# NPaddle.net
KiCad netlist of a schematic drawn in EAGLE
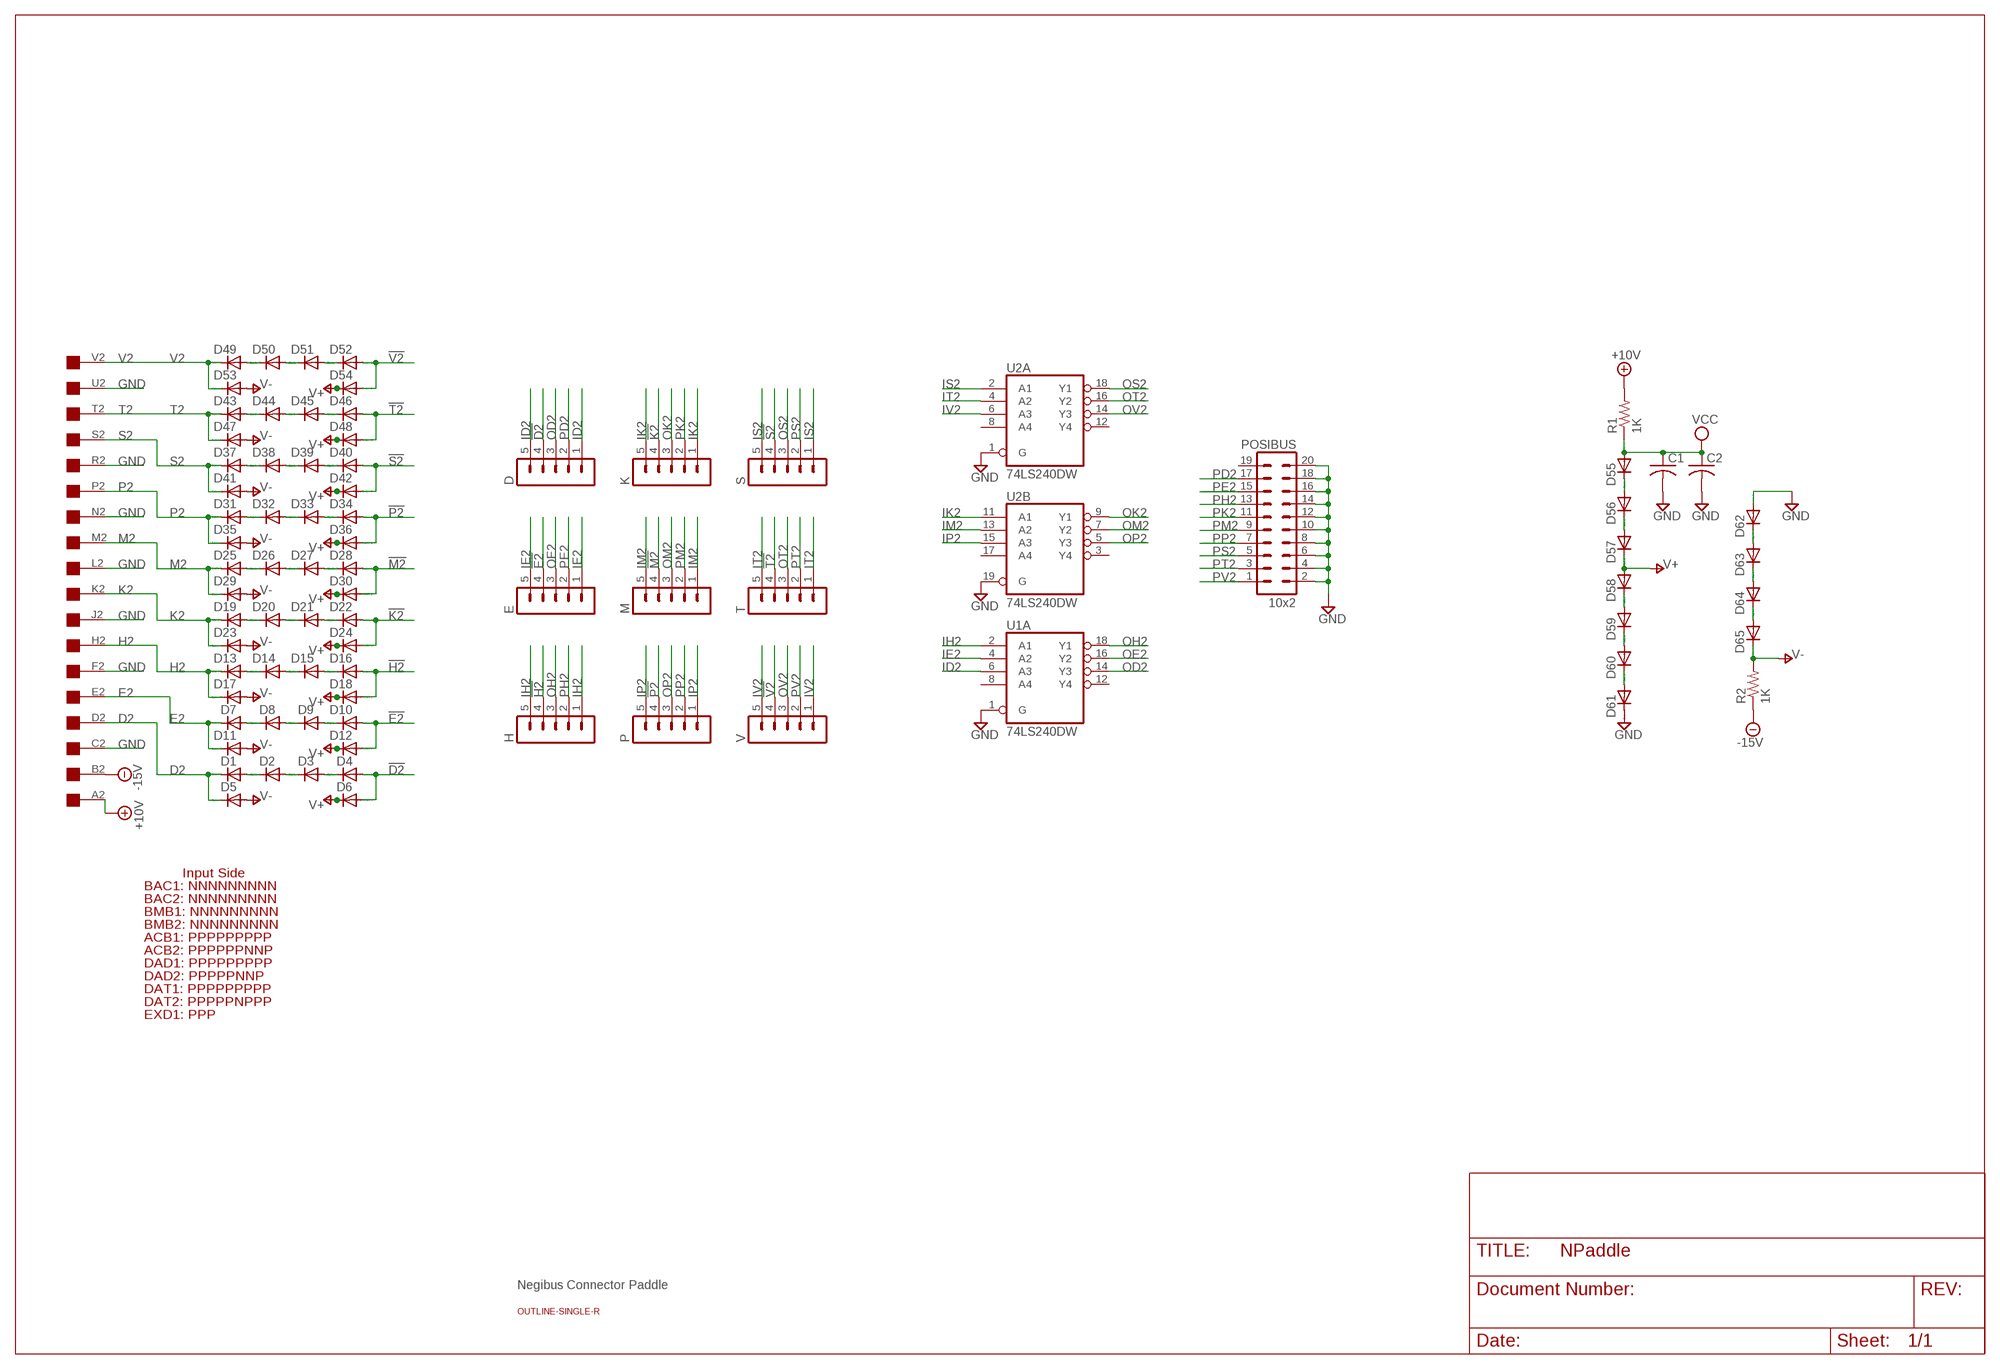
[diagram p0: schematic, sheet 1]

(export (version "E")
  (design (tool "Eeschema 10.0.6"))
  (components
    (comp (ref "C1")
      (value "C-US050-025X075")
      (footprint "eagle-import:C050-025X075")
      (libsource (lib "eagle-import") (part "C-US050-025X075"))
    )
    (comp (ref "C2")
      (value "C-US050-025X075")
      (footprint "eagle-import:C050-025X075")
      (libsource (lib "eagle-import") (part "C-US050-025X075"))
    )
    (comp (ref "D")
      (value "MA05-1")
      (footprint "eagle-import:MA05-1")
      (libsource (lib "eagle-import") (part "MA05-1"))
    )
    (comp (ref "D1")
      (value "1N4148WS")
      (footprint "eagle-import:SOD323-W")
      (libsource (lib "eagle-import") (part "DIODE-SOD323-W"))
    )
    (comp (ref "D2")
      (value "1N4148WS")
      (footprint "eagle-import:SOD323-W")
      (libsource (lib "eagle-import") (part "DIODE-SOD323-W"))
    )
    (comp (ref "D3")
      (value "1N4148WS")
      (footprint "eagle-import:SOD323-W")
      (libsource (lib "eagle-import") (part "DIODE-SOD323-W"))
    )
    (comp (ref "D4")
      (value "1N4148WS")
      (footprint "eagle-import:SOD323-W")
      (libsource (lib "eagle-import") (part "DIODE-SOD323-W"))
    )
    (comp (ref "D5")
      (value "1N4148WS")
      (footprint "eagle-import:SOD323-W")
      (libsource (lib "eagle-import") (part "DIODE-SOD323-W"))
    )
    (comp (ref "D6")
      (value "1N4148WS")
      (footprint "eagle-import:SOD323-W")
      (libsource (lib "eagle-import") (part "DIODE-SOD323-W"))
    )
    (comp (ref "D7")
      (value "1N4148WS")
      (footprint "eagle-import:SOD323-W")
      (libsource (lib "eagle-import") (part "DIODE-SOD323-W"))
    )
    (comp (ref "D8")
      (value "1N4148WS")
      (footprint "eagle-import:SOD323-W")
      (libsource (lib "eagle-import") (part "DIODE-SOD323-W"))
    )
    (comp (ref "D9")
      (value "1N4148WS")
      (footprint "eagle-import:SOD323-W")
      (libsource (lib "eagle-import") (part "DIODE-SOD323-W"))
    )
    (comp (ref "D10")
      (value "1N4148WS")
      (footprint "eagle-import:SOD323-W")
      (libsource (lib "eagle-import") (part "DIODE-SOD323-W"))
    )
    (comp (ref "D11")
      (value "1N4148WS")
      (footprint "eagle-import:SOD323-W")
      (libsource (lib "eagle-import") (part "DIODE-SOD323-W"))
    )
    (comp (ref "D12")
      (value "1N4148WS")
      (footprint "eagle-import:SOD323-W")
      (libsource (lib "eagle-import") (part "DIODE-SOD323-W"))
    )
    (comp (ref "D13")
      (value "1N4148WS")
      (footprint "eagle-import:SOD323-W")
      (libsource (lib "eagle-import") (part "DIODE-SOD323-W"))
    )
    (comp (ref "D14")
      (value "1N4148WS")
      (footprint "eagle-import:SOD323-W")
      (libsource (lib "eagle-import") (part "DIODE-SOD323-W"))
    )
    (comp (ref "D15")
      (value "1N4148WS")
      (footprint "eagle-import:SOD323-W")
      (libsource (lib "eagle-import") (part "DIODE-SOD323-W"))
    )
    (comp (ref "D16")
      (value "1N4148WS")
      (footprint "eagle-import:SOD323-W")
      (libsource (lib "eagle-import") (part "DIODE-SOD323-W"))
    )
    (comp (ref "D17")
      (value "1N4148WS")
      (footprint "eagle-import:SOD323-W")
      (libsource (lib "eagle-import") (part "DIODE-SOD323-W"))
    )
    (comp (ref "D18")
      (value "1N4148WS")
      (footprint "eagle-import:SOD323-W")
      (libsource (lib "eagle-import") (part "DIODE-SOD323-W"))
    )
    (comp (ref "D19")
      (value "1N4148WS")
      (footprint "eagle-import:SOD323-W")
      (libsource (lib "eagle-import") (part "DIODE-SOD323-W"))
    )
    (comp (ref "D20")
      (value "1N4148WS")
      (footprint "eagle-import:SOD323-W")
      (libsource (lib "eagle-import") (part "DIODE-SOD323-W"))
    )
    (comp (ref "D21")
      (value "1N4148WS")
      (footprint "eagle-import:SOD323-W")
      (libsource (lib "eagle-import") (part "DIODE-SOD323-W"))
    )
    (comp (ref "D22")
      (value "1N4148WS")
      (footprint "eagle-import:SOD323-W")
      (libsource (lib "eagle-import") (part "DIODE-SOD323-W"))
    )
    (comp (ref "D23")
      (value "1N4148WS")
      (footprint "eagle-import:SOD323-W")
      (libsource (lib "eagle-import") (part "DIODE-SOD323-W"))
    )
    (comp (ref "D24")
      (value "1N4148WS")
      (footprint "eagle-import:SOD323-W")
      (libsource (lib "eagle-import") (part "DIODE-SOD323-W"))
    )
    (comp (ref "D25")
      (value "1N4148WS")
      (footprint "eagle-import:SOD323-W")
      (libsource (lib "eagle-import") (part "DIODE-SOD323-W"))
    )
    (comp (ref "D26")
      (value "1N4148WS")
      (footprint "eagle-import:SOD323-W")
      (libsource (lib "eagle-import") (part "DIODE-SOD323-W"))
    )
    (comp (ref "D27")
      (value "1N4148WS")
      (footprint "eagle-import:SOD323-W")
      (libsource (lib "eagle-import") (part "DIODE-SOD323-W"))
    )
    (comp (ref "D28")
      (value "1N4148WS")
      (footprint "eagle-import:SOD323-W")
      (libsource (lib "eagle-import") (part "DIODE-SOD323-W"))
    )
    (comp (ref "D29")
      (value "1N4148WS")
      (footprint "eagle-import:SOD323-W")
      (libsource (lib "eagle-import") (part "DIODE-SOD323-W"))
    )
    (comp (ref "D30")
      (value "1N4148WS")
      (footprint "eagle-import:SOD323-W")
      (libsource (lib "eagle-import") (part "DIODE-SOD323-W"))
    )
    (comp (ref "D31")
      (value "1N4148WS")
      (footprint "eagle-import:SOD323-W")
      (libsource (lib "eagle-import") (part "DIODE-SOD323-W"))
    )
    (comp (ref "D32")
      (value "1N4148WS")
      (footprint "eagle-import:SOD323-W")
      (libsource (lib "eagle-import") (part "DIODE-SOD323-W"))
    )
    (comp (ref "D33")
      (value "1N4148WS")
      (footprint "eagle-import:SOD323-W")
      (libsource (lib "eagle-import") (part "DIODE-SOD323-W"))
    )
    (comp (ref "D34")
      (value "1N4148WS")
      (footprint "eagle-import:SOD323-W")
      (libsource (lib "eagle-import") (part "DIODE-SOD323-W"))
    )
    (comp (ref "D35")
      (value "1N4148WS")
      (footprint "eagle-import:SOD323-W")
      (libsource (lib "eagle-import") (part "DIODE-SOD323-W"))
    )
    (comp (ref "D36")
      (value "1N4148WS")
      (footprint "eagle-import:SOD323-W")
      (libsource (lib "eagle-import") (part "DIODE-SOD323-W"))
    )
    (comp (ref "D37")
      (value "1N4148WS")
      (footprint "eagle-import:SOD323-W")
      (libsource (lib "eagle-import") (part "DIODE-SOD323-W"))
    )
    (comp (ref "D38")
      (value "1N4148WS")
      (footprint "eagle-import:SOD323-W")
      (libsource (lib "eagle-import") (part "DIODE-SOD323-W"))
    )
    (comp (ref "D39")
      (value "1N4148WS")
      (footprint "eagle-import:SOD323-W")
      (libsource (lib "eagle-import") (part "DIODE-SOD323-W"))
    )
    (comp (ref "D40")
      (value "1N4148WS")
      (footprint "eagle-import:SOD323-W")
      (libsource (lib "eagle-import") (part "DIODE-SOD323-W"))
    )
    (comp (ref "D41")
      (value "1N4148WS")
      (footprint "eagle-import:SOD323-W")
      (libsource (lib "eagle-import") (part "DIODE-SOD323-W"))
    )
    (comp (ref "D42")
      (value "1N4148WS")
      (footprint "eagle-import:SOD323-W")
      (libsource (lib "eagle-import") (part "DIODE-SOD323-W"))
    )
    (comp (ref "D43")
      (value "1N4148WS")
      (footprint "eagle-import:SOD323-W")
      (libsource (lib "eagle-import") (part "DIODE-SOD323-W"))
    )
    (comp (ref "D44")
      (value "1N4148WS")
      (footprint "eagle-import:SOD323-W")
      (libsource (lib "eagle-import") (part "DIODE-SOD323-W"))
    )
    (comp (ref "D45")
      (value "1N4148WS")
      (footprint "eagle-import:SOD323-W")
      (libsource (lib "eagle-import") (part "DIODE-SOD323-W"))
    )
    (comp (ref "D46")
      (value "1N4148WS")
      (footprint "eagle-import:SOD323-W")
      (libsource (lib "eagle-import") (part "DIODE-SOD323-W"))
    )
    (comp (ref "D47")
      (value "1N4148WS")
      (footprint "eagle-import:SOD323-W")
      (libsource (lib "eagle-import") (part "DIODE-SOD323-W"))
    )
    (comp (ref "D48")
      (value "1N4148WS")
      (footprint "eagle-import:SOD323-W")
      (libsource (lib "eagle-import") (part "DIODE-SOD323-W"))
    )
    (comp (ref "D49")
      (value "1N4148WS")
      (footprint "eagle-import:SOD323-W")
      (libsource (lib "eagle-import") (part "DIODE-SOD323-W"))
    )
    (comp (ref "D50")
      (value "1N4148WS")
      (footprint "eagle-import:SOD323-W")
      (libsource (lib "eagle-import") (part "DIODE-SOD323-W"))
    )
    (comp (ref "D51")
      (value "1N4148WS")
      (footprint "eagle-import:SOD323-W")
      (libsource (lib "eagle-import") (part "DIODE-SOD323-W"))
    )
    (comp (ref "D52")
      (value "1N4148WS")
      (footprint "eagle-import:SOD323-W")
      (libsource (lib "eagle-import") (part "DIODE-SOD323-W"))
    )
    (comp (ref "D53")
      (value "1N4148WS")
      (footprint "eagle-import:SOD323-W")
      (libsource (lib "eagle-import") (part "DIODE-SOD323-W"))
    )
    (comp (ref "D54")
      (value "1N4148WS")
      (footprint "eagle-import:SOD323-W")
      (libsource (lib "eagle-import") (part "DIODE-SOD323-W"))
    )
    (comp (ref "D55")
      (value "1N4148WS")
      (footprint "eagle-import:SOD323-W")
      (libsource (lib "eagle-import") (part "DIODE-SOD323-W"))
    )
    (comp (ref "D56")
      (value "1N4148WS")
      (footprint "eagle-import:SOD323-W")
      (libsource (lib "eagle-import") (part "DIODE-SOD323-W"))
    )
    (comp (ref "D57")
      (value "1N4148WS")
      (footprint "eagle-import:SOD323-W")
      (libsource (lib "eagle-import") (part "DIODE-SOD323-W"))
    )
    (comp (ref "D58")
      (value "1N4148WS")
      (footprint "eagle-import:SOD323-W")
      (libsource (lib "eagle-import") (part "DIODE-SOD323-W"))
    )
    (comp (ref "D59")
      (value "1N4148WS")
      (footprint "eagle-import:SOD323-W")
      (libsource (lib "eagle-import") (part "DIODE-SOD323-W"))
    )
    (comp (ref "D60")
      (value "1N4148WS")
      (footprint "eagle-import:SOD323-W")
      (libsource (lib "eagle-import") (part "DIODE-SOD323-W"))
    )
    (comp (ref "D61")
      (value "1N4148WS")
      (footprint "eagle-import:SOD323-W")
      (libsource (lib "eagle-import") (part "DIODE-SOD323-W"))
    )
    (comp (ref "D62")
      (value "1N4148WS")
      (footprint "eagle-import:SOD323-W")
      (libsource (lib "eagle-import") (part "DIODE-SOD323-W"))
    )
    (comp (ref "D63")
      (value "1N4148WS")
      (footprint "eagle-import:SOD323-W")
      (libsource (lib "eagle-import") (part "DIODE-SOD323-W"))
    )
    (comp (ref "D64")
      (value "1N4148WS")
      (footprint "eagle-import:SOD323-W")
      (libsource (lib "eagle-import") (part "DIODE-SOD323-W"))
    )
    (comp (ref "D65")
      (value "1N4148WS")
      (footprint "eagle-import:SOD323-W")
      (libsource (lib "eagle-import") (part "DIODE-SOD323-W"))
    )
    (comp (ref "E")
      (value "MA05-1")
      (footprint "eagle-import:MA05-1")
      (libsource (lib "eagle-import") (part "MA05-1"))
    )
    (comp (ref "H")
      (value "MA05-1")
      (footprint "eagle-import:MA05-1")
      (libsource (lib "eagle-import") (part "MA05-1"))
    )
    (comp (ref "K")
      (value "MA05-1")
      (footprint "eagle-import:MA05-1")
      (libsource (lib "eagle-import") (part "MA05-1"))
    )
    (comp (ref "M")
      (value "MA05-1")
      (footprint "eagle-import:MA05-1")
      (libsource (lib "eagle-import") (part "MA05-1"))
    )
    (comp (ref "P")
      (value "MA05-1")
      (footprint "eagle-import:MA05-1")
      (libsource (lib "eagle-import") (part "MA05-1"))
    )
    (comp (ref "POSIBUS")
      (value "10x2")
      (footprint "eagle-import:MA10-2")
      (libsource (lib "eagle-import") (part "MA10-2"))
    )
    (comp (ref "R1")
      (value "1K")
      (footprint "eagle-import:0207_10")
      (libsource (lib "eagle-import") (part "R-US_0207/10"))
    )
    (comp (ref "R2")
      (value "1K")
      (footprint "eagle-import:0207_10")
      (libsource (lib "eagle-import") (part "R-US_0207/10"))
    )
    (comp (ref "S")
      (value "MA05-1")
      (footprint "eagle-import:MA05-1")
      (libsource (lib "eagle-import") (part "MA05-1"))
    )
    (comp (ref "T")
      (value "MA05-1")
      (footprint "eagle-import:MA05-1")
      (libsource (lib "eagle-import") (part "MA05-1"))
    )
    (comp (ref "U$1")
      (value "OUTLINE-SINGLE-R")
      (footprint "eagle-import:SINGLE-R")
      (libsource (lib "eagle-import") (part "OUTLINE-SINGLE-R"))
    )
    (comp (ref "U$2")
      (value "EDGE")
      (footprint "eagle-import:EDGE-CON2")
      (libsource (lib "eagle-import") (part "SINGLE"))
    )
    (comp (ref "U1")
      (value "74LS240DW")
      (footprint "eagle-import:SO20W")
      (libsource (lib "eagle-import") (part "74240DWLS"))
    )
    (comp (ref "U2")
      (value "74LS240DW")
      (footprint "eagle-import:SO20W")
      (libsource (lib "eagle-import") (part "74240DWLS"))
    )
    (comp (ref "V")
      (value "MA05-1")
      (footprint "eagle-import:MA05-1")
      (libsource (lib "eagle-import") (part "MA05-1"))
    )
  )
  (nets
    (net (code "1") (name "+10V") (class "Default")
      (node (ref "R1") (pin "2") (pinfunction "2_2") (pintype "passive"))
      (node (ref "U$2") (pin "A2") (pinfunction "1_A2") (pintype "bidirectional"))
    )
    (net (code "2") (name "-15V") (class "Default")
      (node (ref "R2") (pin "1") (pinfunction "1_1") (pintype "passive"))
      (node (ref "U$2") (pin "B2") (pinfunction "1_B2") (pintype "bidirectional"))
    )
    (net (code "3") (name "/D2") (class "Default")
      (node (ref "D1") (pin "C") (pinfunction "C_C") (pintype "passive"))
      (node (ref "D5") (pin "C") (pinfunction "C_C") (pintype "passive"))
      (node (ref "U$2") (pin "D2") (pinfunction "1_D2") (pintype "bidirectional"))
    )
    (net (code "4") (name "/E2") (class "Default")
      (node (ref "D11") (pin "C") (pinfunction "C_C") (pintype "passive"))
      (node (ref "D7") (pin "C") (pinfunction "C_C") (pintype "passive"))
      (node (ref "U$2") (pin "E2") (pinfunction "1_E2") (pintype "bidirectional"))
    )
    (net (code "5") (name "/H2") (class "Default")
      (node (ref "D13") (pin "C") (pinfunction "C_C") (pintype "passive"))
      (node (ref "D17") (pin "C") (pinfunction "C_C") (pintype "passive"))
      (node (ref "U$2") (pin "H2") (pinfunction "1_H2") (pintype "bidirectional"))
    )
    (net (code "6") (name "/ID2") (class "Default")
      (node (ref "D") (pin "1") (pinfunction "1_1") (pintype "passive"))
      (node (ref "D") (pin "5") (pinfunction "5_5") (pintype "passive"))
      (node (ref "U1") (pin "6") (pinfunction "A3_6") (pintype "input"))
    )
    (net (code "7") (name "/IE2") (class "Default")
      (node (ref "E") (pin "1") (pinfunction "1_1") (pintype "passive"))
      (node (ref "E") (pin "5") (pinfunction "5_5") (pintype "passive"))
      (node (ref "U1") (pin "4") (pinfunction "A2_4") (pintype "input"))
    )
    (net (code "8") (name "/IH2") (class "Default")
      (node (ref "H") (pin "1") (pinfunction "1_1") (pintype "passive"))
      (node (ref "H") (pin "5") (pinfunction "5_5") (pintype "passive"))
      (node (ref "U1") (pin "2") (pinfunction "A1_2") (pintype "input"))
    )
    (net (code "9") (name "/IK2") (class "Default")
      (node (ref "K") (pin "1") (pinfunction "1_1") (pintype "passive"))
      (node (ref "K") (pin "5") (pinfunction "5_5") (pintype "passive"))
      (node (ref "U2") (pin "11") (pinfunction "A1_11") (pintype "input"))
    )
    (net (code "10") (name "/IM2") (class "Default")
      (node (ref "M") (pin "1") (pinfunction "1_1") (pintype "passive"))
      (node (ref "M") (pin "5") (pinfunction "5_5") (pintype "passive"))
      (node (ref "U2") (pin "13") (pinfunction "A2_13") (pintype "input"))
    )
    (net (code "11") (name "/IP2") (class "Default")
      (node (ref "P") (pin "1") (pinfunction "1_1") (pintype "passive"))
      (node (ref "P") (pin "5") (pinfunction "5_5") (pintype "passive"))
      (node (ref "U2") (pin "15") (pinfunction "A3_15") (pintype "input"))
    )
    (net (code "12") (name "/IS2") (class "Default")
      (node (ref "S") (pin "1") (pinfunction "1_1") (pintype "passive"))
      (node (ref "S") (pin "5") (pinfunction "5_5") (pintype "passive"))
      (node (ref "U2") (pin "2") (pinfunction "A1_2") (pintype "input"))
    )
    (net (code "13") (name "/IT2") (class "Default")
      (node (ref "T") (pin "1") (pinfunction "1_1") (pintype "passive"))
      (node (ref "T") (pin "5") (pinfunction "5_5") (pintype "passive"))
      (node (ref "U2") (pin "4") (pinfunction "A2_4") (pintype "input"))
    )
    (net (code "14") (name "/IV2") (class "Default")
      (node (ref "U2") (pin "6") (pinfunction "A3_6") (pintype "input"))
      (node (ref "V") (pin "1") (pinfunction "1_1") (pintype "passive"))
      (node (ref "V") (pin "5") (pinfunction "5_5") (pintype "passive"))
    )
    (net (code "15") (name "/K2") (class "Default")
      (node (ref "D19") (pin "C") (pinfunction "C_C") (pintype "passive"))
      (node (ref "D23") (pin "C") (pinfunction "C_C") (pintype "passive"))
      (node (ref "U$2") (pin "K2") (pinfunction "1_K2") (pintype "bidirectional"))
    )
    (net (code "16") (name "/M2") (class "Default")
      (node (ref "D25") (pin "C") (pinfunction "C_C") (pintype "passive"))
      (node (ref "D29") (pin "C") (pinfunction "C_C") (pintype "passive"))
      (node (ref "U$2") (pin "M2") (pinfunction "1_M2") (pintype "bidirectional"))
    )
    (net (code "17") (name "/OD2") (class "Default")
      (node (ref "D") (pin "3") (pinfunction "3_3") (pintype "passive"))
      (node (ref "U1") (pin "14") (pinfunction "Y3_14") (pintype "tri_state"))
    )
    (net (code "18") (name "/OE2") (class "Default")
      (node (ref "E") (pin "3") (pinfunction "3_3") (pintype "passive"))
      (node (ref "U1") (pin "16") (pinfunction "Y2_16") (pintype "tri_state"))
    )
    (net (code "19") (name "/OH2") (class "Default")
      (node (ref "H") (pin "3") (pinfunction "3_3") (pintype "passive"))
      (node (ref "U1") (pin "18") (pinfunction "Y1_18") (pintype "tri_state"))
    )
    (net (code "20") (name "/OK2") (class "Default")
      (node (ref "K") (pin "3") (pinfunction "3_3") (pintype "passive"))
      (node (ref "U2") (pin "9") (pinfunction "Y1_9") (pintype "tri_state"))
    )
    (net (code "21") (name "/OM2") (class "Default")
      (node (ref "M") (pin "3") (pinfunction "3_3") (pintype "passive"))
      (node (ref "U2") (pin "7") (pinfunction "Y2_7") (pintype "tri_state"))
    )
    (net (code "22") (name "/OP2") (class "Default")
      (node (ref "P") (pin "3") (pinfunction "3_3") (pintype "passive"))
      (node (ref "U2") (pin "5") (pinfunction "Y3_5") (pintype "tri_state"))
    )
    (net (code "23") (name "/OS2") (class "Default")
      (node (ref "S") (pin "3") (pinfunction "3_3") (pintype "passive"))
      (node (ref "U2") (pin "18") (pinfunction "Y1_18") (pintype "tri_state"))
    )
    (net (code "24") (name "/OT2") (class "Default")
      (node (ref "T") (pin "3") (pinfunction "3_3") (pintype "passive"))
      (node (ref "U2") (pin "16") (pinfunction "Y2_16") (pintype "tri_state"))
    )
    (net (code "25") (name "/OV2") (class "Default")
      (node (ref "U2") (pin "14") (pinfunction "Y3_14") (pintype "tri_state"))
      (node (ref "V") (pin "3") (pinfunction "3_3") (pintype "passive"))
    )
    (net (code "26") (name "/P2") (class "Default")
      (node (ref "D31") (pin "C") (pinfunction "C_C") (pintype "passive"))
      (node (ref "D35") (pin "C") (pinfunction "C_C") (pintype "passive"))
      (node (ref "U$2") (pin "P2") (pinfunction "1_P2") (pintype "bidirectional"))
    )
    (net (code "27") (name "/PD2") (class "Default")
      (node (ref "D") (pin "2") (pinfunction "2_2") (pintype "passive"))
      (node (ref "POSIBUS") (pin "17") (pinfunction "17_17") (pintype "passive"))
    )
    (net (code "28") (name "/PE2") (class "Default")
      (node (ref "E") (pin "2") (pinfunction "2_2") (pintype "passive"))
      (node (ref "POSIBUS") (pin "15") (pinfunction "15_15") (pintype "passive"))
    )
    (net (code "29") (name "/PH2") (class "Default")
      (node (ref "H") (pin "2") (pinfunction "2_2") (pintype "passive"))
      (node (ref "POSIBUS") (pin "13") (pinfunction "13_13") (pintype "passive"))
    )
    (net (code "30") (name "/PK2") (class "Default")
      (node (ref "K") (pin "2") (pinfunction "2_2") (pintype "passive"))
      (node (ref "POSIBUS") (pin "11") (pinfunction "11_11") (pintype "passive"))
    )
    (net (code "31") (name "/PM2") (class "Default")
      (node (ref "M") (pin "2") (pinfunction "2_2") (pintype "passive"))
      (node (ref "POSIBUS") (pin "9") (pinfunction "9_9") (pintype "passive"))
    )
    (net (code "32") (name "/PP2") (class "Default")
      (node (ref "P") (pin "2") (pinfunction "2_2") (pintype "passive"))
      (node (ref "POSIBUS") (pin "7") (pinfunction "7_7") (pintype "passive"))
    )
    (net (code "33") (name "/PS2") (class "Default")
      (node (ref "POSIBUS") (pin "5") (pinfunction "5_5") (pintype "passive"))
      (node (ref "S") (pin "2") (pinfunction "2_2") (pintype "passive"))
    )
    (net (code "34") (name "/PT2") (class "Default")
      (node (ref "POSIBUS") (pin "3") (pinfunction "3_3") (pintype "passive"))
      (node (ref "T") (pin "2") (pinfunction "2_2") (pintype "passive"))
    )
    (net (code "35") (name "/PV2") (class "Default")
      (node (ref "POSIBUS") (pin "1") (pinfunction "1_1") (pintype "passive"))
      (node (ref "V") (pin "2") (pinfunction "2_2") (pintype "passive"))
    )
    (net (code "36") (name "/S2") (class "Default")
      (node (ref "D37") (pin "C") (pinfunction "C_C") (pintype "passive"))
      (node (ref "D41") (pin "C") (pinfunction "C_C") (pintype "passive"))
      (node (ref "U$2") (pin "S2") (pinfunction "1_S2") (pintype "bidirectional"))
    )
    (net (code "37") (name "/T2") (class "Default")
      (node (ref "D43") (pin "C") (pinfunction "C_C") (pintype "passive"))
      (node (ref "D47") (pin "C") (pinfunction "C_C") (pintype "passive"))
      (node (ref "U$2") (pin "T2") (pinfunction "1_T2") (pintype "bidirectional"))
    )
    (net (code "38") (name "/V2") (class "Default")
      (node (ref "D49") (pin "C") (pinfunction "C_C") (pintype "passive"))
      (node (ref "D53") (pin "C") (pinfunction "C_C") (pintype "passive"))
      (node (ref "U$2") (pin "V2") (pinfunction "1_V2") (pintype "bidirectional"))
    )
    (net (code "39") (name "/~{D2}") (class "Default")
      (node (ref "D") (pin "4") (pinfunction "4_4") (pintype "passive"))
      (node (ref "D4") (pin "A") (pinfunction "A_A") (pintype "passive"))
      (node (ref "D6") (pin "A") (pinfunction "A_A") (pintype "passive"))
    )
    (net (code "40") (name "/~{E2}") (class "Default")
      (node (ref "D10") (pin "A") (pinfunction "A_A") (pintype "passive"))
      (node (ref "D12") (pin "A") (pinfunction "A_A") (pintype "passive"))
      (node (ref "E") (pin "4") (pinfunction "4_4") (pintype "passive"))
    )
    (net (code "41") (name "/~{H2}") (class "Default")
      (node (ref "D16") (pin "A") (pinfunction "A_A") (pintype "passive"))
      (node (ref "D18") (pin "A") (pinfunction "A_A") (pintype "passive"))
      (node (ref "H") (pin "4") (pinfunction "4_4") (pintype "passive"))
    )
    (net (code "42") (name "/~{K2}") (class "Default")
      (node (ref "D22") (pin "A") (pinfunction "A_A") (pintype "passive"))
      (node (ref "D24") (pin "A") (pinfunction "A_A") (pintype "passive"))
      (node (ref "K") (pin "4") (pinfunction "4_4") (pintype "passive"))
    )
    (net (code "43") (name "/~{M2}") (class "Default")
      (node (ref "D28") (pin "A") (pinfunction "A_A") (pintype "passive"))
      (node (ref "D30") (pin "A") (pinfunction "A_A") (pintype "passive"))
      (node (ref "M") (pin "4") (pinfunction "4_4") (pintype "passive"))
    )
    (net (code "44") (name "/~{P2}") (class "Default")
      (node (ref "D34") (pin "A") (pinfunction "A_A") (pintype "passive"))
      (node (ref "D36") (pin "A") (pinfunction "A_A") (pintype "passive"))
      (node (ref "P") (pin "4") (pinfunction "4_4") (pintype "passive"))
    )
    (net (code "45") (name "/~{S2}") (class "Default")
      (node (ref "D40") (pin "A") (pinfunction "A_A") (pintype "passive"))
      (node (ref "D42") (pin "A") (pinfunction "A_A") (pintype "passive"))
      (node (ref "S") (pin "4") (pinfunction "4_4") (pintype "passive"))
    )
    (net (code "46") (name "/~{T2}") (class "Default")
      (node (ref "D46") (pin "A") (pinfunction "A_A") (pintype "passive"))
      (node (ref "D48") (pin "A") (pinfunction "A_A") (pintype "passive"))
      (node (ref "T") (pin "4") (pinfunction "4_4") (pintype "passive"))
    )
    (net (code "47") (name "/~{V2}") (class "Default")
      (node (ref "D52") (pin "A") (pinfunction "A_A") (pintype "passive"))
      (node (ref "D54") (pin "A") (pinfunction "A_A") (pintype "passive"))
      (node (ref "V") (pin "4") (pinfunction "4_4") (pintype "passive"))
    )
    (net (code "48") (name "GND") (class "Default")
      (node (ref "C1") (pin "2") (pinfunction "2_2") (pintype "passive"))
      (node (ref "C2") (pin "2") (pinfunction "2_2") (pintype "passive"))
      (node (ref "D61") (pin "C") (pinfunction "C_C") (pintype "passive"))
      (node (ref "D62") (pin "A") (pinfunction "A_A") (pintype "passive"))
      (node (ref "POSIBUS") (pin "10") (pinfunction "10_10") (pintype "passive"))
      (node (ref "POSIBUS") (pin "12") (pinfunction "12_12") (pintype "passive"))
      (node (ref "POSIBUS") (pin "14") (pinfunction "14_14") (pintype "passive"))
      (node (ref "POSIBUS") (pin "16") (pinfunction "16_16") (pintype "passive"))
      (node (ref "POSIBUS") (pin "18") (pinfunction "18_18") (pintype "passive"))
      (node (ref "POSIBUS") (pin "2") (pinfunction "2_2") (pintype "passive"))
      (node (ref "POSIBUS") (pin "20") (pinfunction "20_20") (pintype "passive"))
      (node (ref "POSIBUS") (pin "4") (pinfunction "4_4") (pintype "passive"))
      (node (ref "POSIBUS") (pin "6") (pinfunction "6_6") (pintype "passive"))
      (node (ref "POSIBUS") (pin "8") (pinfunction "8_8") (pintype "passive"))
      (node (ref "U$2") (pin "C2") (pinfunction "1_C2") (pintype "bidirectional"))
      (node (ref "U$2") (pin "F2") (pinfunction "1_F2") (pintype "bidirectional"))
      (node (ref "U$2") (pin "J2") (pinfunction "1_J2") (pintype "bidirectional"))
      (node (ref "U$2") (pin "L2") (pinfunction "1_L2") (pintype "bidirectional"))
      (node (ref "U$2") (pin "N2") (pinfunction "1_N2") (pintype "bidirectional"))
      (node (ref "U$2") (pin "R2") (pinfunction "1_R2") (pintype "bidirectional"))
      (node (ref "U$2") (pin "U2") (pinfunction "1_U2") (pintype "bidirectional"))
      (node (ref "U1") (pin "1") (pinfunction "G_1") (pintype "input"))
      (node (ref "U2") (pin "1") (pinfunction "G_1") (pintype "input"))
      (node (ref "U2") (pin "19") (pinfunction "G_19") (pintype "input"))
    )
    (net (code "49") (name "Net-(D1-PadA)") (class "Default")
      (node (ref "D1") (pin "A") (pinfunction "A_A") (pintype "passive"))
      (node (ref "D2") (pin "C") (pinfunction "C_C") (pintype "passive"))
    )
    (net (code "50") (name "Net-(D2-PadA)") (class "Default")
      (node (ref "D2") (pin "A") (pinfunction "A_A") (pintype "passive"))
      (node (ref "D3") (pin "C") (pinfunction "C_C") (pintype "passive"))
    )
    (net (code "51") (name "Net-(D3-PadA)") (class "Default")
      (node (ref "D3") (pin "A") (pinfunction "A_A") (pintype "passive"))
      (node (ref "D4") (pin "C") (pinfunction "C_C") (pintype "passive"))
    )
    (net (code "52") (name "Net-(D7-PadA)") (class "Default")
      (node (ref "D7") (pin "A") (pinfunction "A_A") (pintype "passive"))
      (node (ref "D8") (pin "C") (pinfunction "C_C") (pintype "passive"))
    )
    (net (code "53") (name "Net-(D8-PadA)") (class "Default")
      (node (ref "D8") (pin "A") (pinfunction "A_A") (pintype "passive"))
      (node (ref "D9") (pin "C") (pinfunction "C_C") (pintype "passive"))
    )
    (net (code "54") (name "Net-(D10-PadC)") (class "Default")
      (node (ref "D10") (pin "C") (pinfunction "C_C") (pintype "passive"))
      (node (ref "D9") (pin "A") (pinfunction "A_A") (pintype "passive"))
    )
    (net (code "55") (name "Net-(D13-PadA)") (class "Default")
      (node (ref "D13") (pin "A") (pinfunction "A_A") (pintype "passive"))
      (node (ref "D14") (pin "C") (pinfunction "C_C") (pintype "passive"))
    )
    (net (code "56") (name "Net-(D14-PadA)") (class "Default")
      (node (ref "D14") (pin "A") (pinfunction "A_A") (pintype "passive"))
      (node (ref "D15") (pin "C") (pinfunction "C_C") (pintype "passive"))
    )
    (net (code "57") (name "Net-(D15-PadA)") (class "Default")
      (node (ref "D15") (pin "A") (pinfunction "A_A") (pintype "passive"))
      (node (ref "D16") (pin "C") (pinfunction "C_C") (pintype "passive"))
    )
    (net (code "58") (name "Net-(D19-PadA)") (class "Default")
      (node (ref "D19") (pin "A") (pinfunction "A_A") (pintype "passive"))
      (node (ref "D20") (pin "C") (pinfunction "C_C") (pintype "passive"))
    )
    (net (code "59") (name "Net-(D20-PadA)") (class "Default")
      (node (ref "D20") (pin "A") (pinfunction "A_A") (pintype "passive"))
      (node (ref "D21") (pin "C") (pinfunction "C_C") (pintype "passive"))
    )
    (net (code "60") (name "Net-(D21-PadA)") (class "Default")
      (node (ref "D21") (pin "A") (pinfunction "A_A") (pintype "passive"))
      (node (ref "D22") (pin "C") (pinfunction "C_C") (pintype "passive"))
    )
    (net (code "61") (name "Net-(D25-PadA)") (class "Default")
      (node (ref "D25") (pin "A") (pinfunction "A_A") (pintype "passive"))
      (node (ref "D26") (pin "C") (pinfunction "C_C") (pintype "passive"))
    )
    (net (code "62") (name "Net-(D26-PadA)") (class "Default")
      (node (ref "D26") (pin "A") (pinfunction "A_A") (pintype "passive"))
      (node (ref "D27") (pin "C") (pinfunction "C_C") (pintype "passive"))
    )
    (net (code "63") (name "Net-(D27-PadA)") (class "Default")
      (node (ref "D27") (pin "A") (pinfunction "A_A") (pintype "passive"))
      (node (ref "D28") (pin "C") (pinfunction "C_C") (pintype "passive"))
    )
    (net (code "64") (name "Net-(D31-PadA)") (class "Default")
      (node (ref "D31") (pin "A") (pinfunction "A_A") (pintype "passive"))
      (node (ref "D32") (pin "C") (pinfunction "C_C") (pintype "passive"))
    )
    (net (code "65") (name "Net-(D32-PadA)") (class "Default")
      (node (ref "D32") (pin "A") (pinfunction "A_A") (pintype "passive"))
      (node (ref "D33") (pin "C") (pinfunction "C_C") (pintype "passive"))
    )
    (net (code "66") (name "Net-(D33-PadA)") (class "Default")
      (node (ref "D33") (pin "A") (pinfunction "A_A") (pintype "passive"))
      (node (ref "D34") (pin "C") (pinfunction "C_C") (pintype "passive"))
    )
    (net (code "67") (name "Net-(D37-PadA)") (class "Default")
      (node (ref "D37") (pin "A") (pinfunction "A_A") (pintype "passive"))
      (node (ref "D38") (pin "C") (pinfunction "C_C") (pintype "passive"))
    )
    (net (code "68") (name "Net-(D38-PadA)") (class "Default")
      (node (ref "D38") (pin "A") (pinfunction "A_A") (pintype "passive"))
      (node (ref "D39") (pin "C") (pinfunction "C_C") (pintype "passive"))
    )
    (net (code "69") (name "Net-(D39-PadA)") (class "Default")
      (node (ref "D39") (pin "A") (pinfunction "A_A") (pintype "passive"))
      (node (ref "D40") (pin "C") (pinfunction "C_C") (pintype "passive"))
    )
    (net (code "70") (name "Net-(D43-PadA)") (class "Default")
      (node (ref "D43") (pin "A") (pinfunction "A_A") (pintype "passive"))
      (node (ref "D44") (pin "C") (pinfunction "C_C") (pintype "passive"))
    )
    (net (code "71") (name "Net-(D44-PadA)") (class "Default")
      (node (ref "D44") (pin "A") (pinfunction "A_A") (pintype "passive"))
      (node (ref "D45") (pin "C") (pinfunction "C_C") (pintype "passive"))
    )
    (net (code "72") (name "Net-(D45-PadA)") (class "Default")
      (node (ref "D45") (pin "A") (pinfunction "A_A") (pintype "passive"))
      (node (ref "D46") (pin "C") (pinfunction "C_C") (pintype "passive"))
    )
    (net (code "73") (name "Net-(D49-PadA)") (class "Default")
      (node (ref "D49") (pin "A") (pinfunction "A_A") (pintype "passive"))
      (node (ref "D50") (pin "C") (pinfunction "C_C") (pintype "passive"))
    )
    (net (code "74") (name "Net-(D50-PadA)") (class "Default")
      (node (ref "D50") (pin "A") (pinfunction "A_A") (pintype "passive"))
      (node (ref "D51") (pin "C") (pinfunction "C_C") (pintype "passive"))
    )
    (net (code "75") (name "Net-(D51-PadA)") (class "Default")
      (node (ref "D51") (pin "A") (pinfunction "A_A") (pintype "passive"))
      (node (ref "D52") (pin "C") (pinfunction "C_C") (pintype "passive"))
    )
    (net (code "76") (name "Net-(D55-PadC)") (class "Default")
      (node (ref "D55") (pin "C") (pinfunction "C_C") (pintype "passive"))
      (node (ref "D56") (pin "A") (pinfunction "A_A") (pintype "passive"))
    )
    (net (code "77") (name "Net-(D56-PadC)") (class "Default")
      (node (ref "D56") (pin "C") (pinfunction "C_C") (pintype "passive"))
      (node (ref "D57") (pin "A") (pinfunction "A_A") (pintype "passive"))
    )
    (net (code "78") (name "Net-(D58-PadC)") (class "Default")
      (node (ref "D58") (pin "C") (pinfunction "C_C") (pintype "passive"))
      (node (ref "D59") (pin "A") (pinfunction "A_A") (pintype "passive"))
    )
    (net (code "79") (name "Net-(D59-PadC)") (class "Default")
      (node (ref "D59") (pin "C") (pinfunction "C_C") (pintype "passive"))
      (node (ref "D60") (pin "A") (pinfunction "A_A") (pintype "passive"))
    )
    (net (code "80") (name "Net-(D60-PadC)") (class "Default")
      (node (ref "D60") (pin "C") (pinfunction "C_C") (pintype "passive"))
      (node (ref "D61") (pin "A") (pinfunction "A_A") (pintype "passive"))
    )
    (net (code "81") (name "Net-(D62-PadC)") (class "Default")
      (node (ref "D62") (pin "C") (pinfunction "C_C") (pintype "passive"))
      (node (ref "D63") (pin "A") (pinfunction "A_A") (pintype "passive"))
    )
    (net (code "82") (name "Net-(D63-PadC)") (class "Default")
      (node (ref "D63") (pin "C") (pinfunction "C_C") (pintype "passive"))
      (node (ref "D64") (pin "A") (pinfunction "A_A") (pintype "passive"))
    )
    (net (code "83") (name "Net-(D64-PadC)") (class "Default")
      (node (ref "D64") (pin "C") (pinfunction "C_C") (pintype "passive"))
      (node (ref "D65") (pin "A") (pinfunction "A_A") (pintype "passive"))
    )
    (net (code "84") (name "V+") (class "Default")
      (node (ref "D12") (pin "C") (pinfunction "C_C") (pintype "passive"))
      (node (ref "D18") (pin "C") (pinfunction "C_C") (pintype "passive"))
      (node (ref "D24") (pin "C") (pinfunction "C_C") (pintype "passive"))
      (node (ref "D30") (pin "C") (pinfunction "C_C") (pintype "passive"))
      (node (ref "D36") (pin "C") (pinfunction "C_C") (pintype "passive"))
      (node (ref "D42") (pin "C") (pinfunction "C_C") (pintype "passive"))
      (node (ref "D48") (pin "C") (pinfunction "C_C") (pintype "passive"))
      (node (ref "D54") (pin "C") (pinfunction "C_C") (pintype "passive"))
      (node (ref "D57") (pin "C") (pinfunction "C_C") (pintype "passive"))
      (node (ref "D58") (pin "A") (pinfunction "A_A") (pintype "passive"))
      (node (ref "D6") (pin "C") (pinfunction "C_C") (pintype "passive"))
    )
    (net (code "85") (name "V-") (class "Default")
      (node (ref "D11") (pin "A") (pinfunction "A_A") (pintype "passive"))
      (node (ref "D17") (pin "A") (pinfunction "A_A") (pintype "passive"))
      (node (ref "D23") (pin "A") (pinfunction "A_A") (pintype "passive"))
      (node (ref "D29") (pin "A") (pinfunction "A_A") (pintype "passive"))
      (node (ref "D35") (pin "A") (pinfunction "A_A") (pintype "passive"))
      (node (ref "D41") (pin "A") (pinfunction "A_A") (pintype "passive"))
      (node (ref "D47") (pin "A") (pinfunction "A_A") (pintype "passive"))
      (node (ref "D5") (pin "A") (pinfunction "A_A") (pintype "passive"))
      (node (ref "D53") (pin "A") (pinfunction "A_A") (pintype "passive"))
      (node (ref "D65") (pin "C") (pinfunction "C_C") (pintype "passive"))
      (node (ref "R2") (pin "2") (pinfunction "2_2") (pintype "passive"))
    )
    (net (code "86") (name "VCC") (class "Default")
      (node (ref "C1") (pin "1") (pinfunction "1_1") (pintype "passive"))
      (node (ref "C2") (pin "1") (pinfunction "1_1") (pintype "passive"))
      (node (ref "D55") (pin "A") (pinfunction "A_A") (pintype "passive"))
      (node (ref "R1") (pin "1") (pinfunction "1_1") (pintype "passive"))
    )
    (net (code "87") (name "unconnected-(POSIBUS-Pad19)") (class "Default")
      (node (ref "POSIBUS") (pin "19") (pinfunction "19_19") (pintype "passive"))
    )
    (net (code "88") (name "unconnected-(U1A-A4-Pad8)") (class "Default")
      (node (ref "U1") (pin "8") (pinfunction "A4_8") (pintype "input"))
    )
    (net (code "89") (name "unconnected-(U1A-Y4-Pad12)") (class "Default")
      (node (ref "U1") (pin "12") (pinfunction "Y4_12") (pintype "tri_state"))
    )
    (net (code "90") (name "unconnected-(U2A-A4-Pad8)") (class "Default")
      (node (ref "U2") (pin "8") (pinfunction "A4_8") (pintype "input"))
    )
    (net (code "91") (name "unconnected-(U2A-Y4-Pad12)") (class "Default")
      (node (ref "U2") (pin "12") (pinfunction "Y4_12") (pintype "tri_state"))
    )
    (net (code "92") (name "unconnected-(U2B-A4-Pad17)") (class "Default")
      (node (ref "U2") (pin "17") (pinfunction "A4_17") (pintype "input"))
    )
    (net (code "93") (name "unconnected-(U2B-Y4-Pad3)") (class "Default")
      (node (ref "U2") (pin "3") (pinfunction "Y4_3") (pintype "tri_state"))
    )
  )
)
